# CSI2-ZCU106-EVK-1_Rev01.net
KiCad netlist of a schematic drawn in Altium Designer
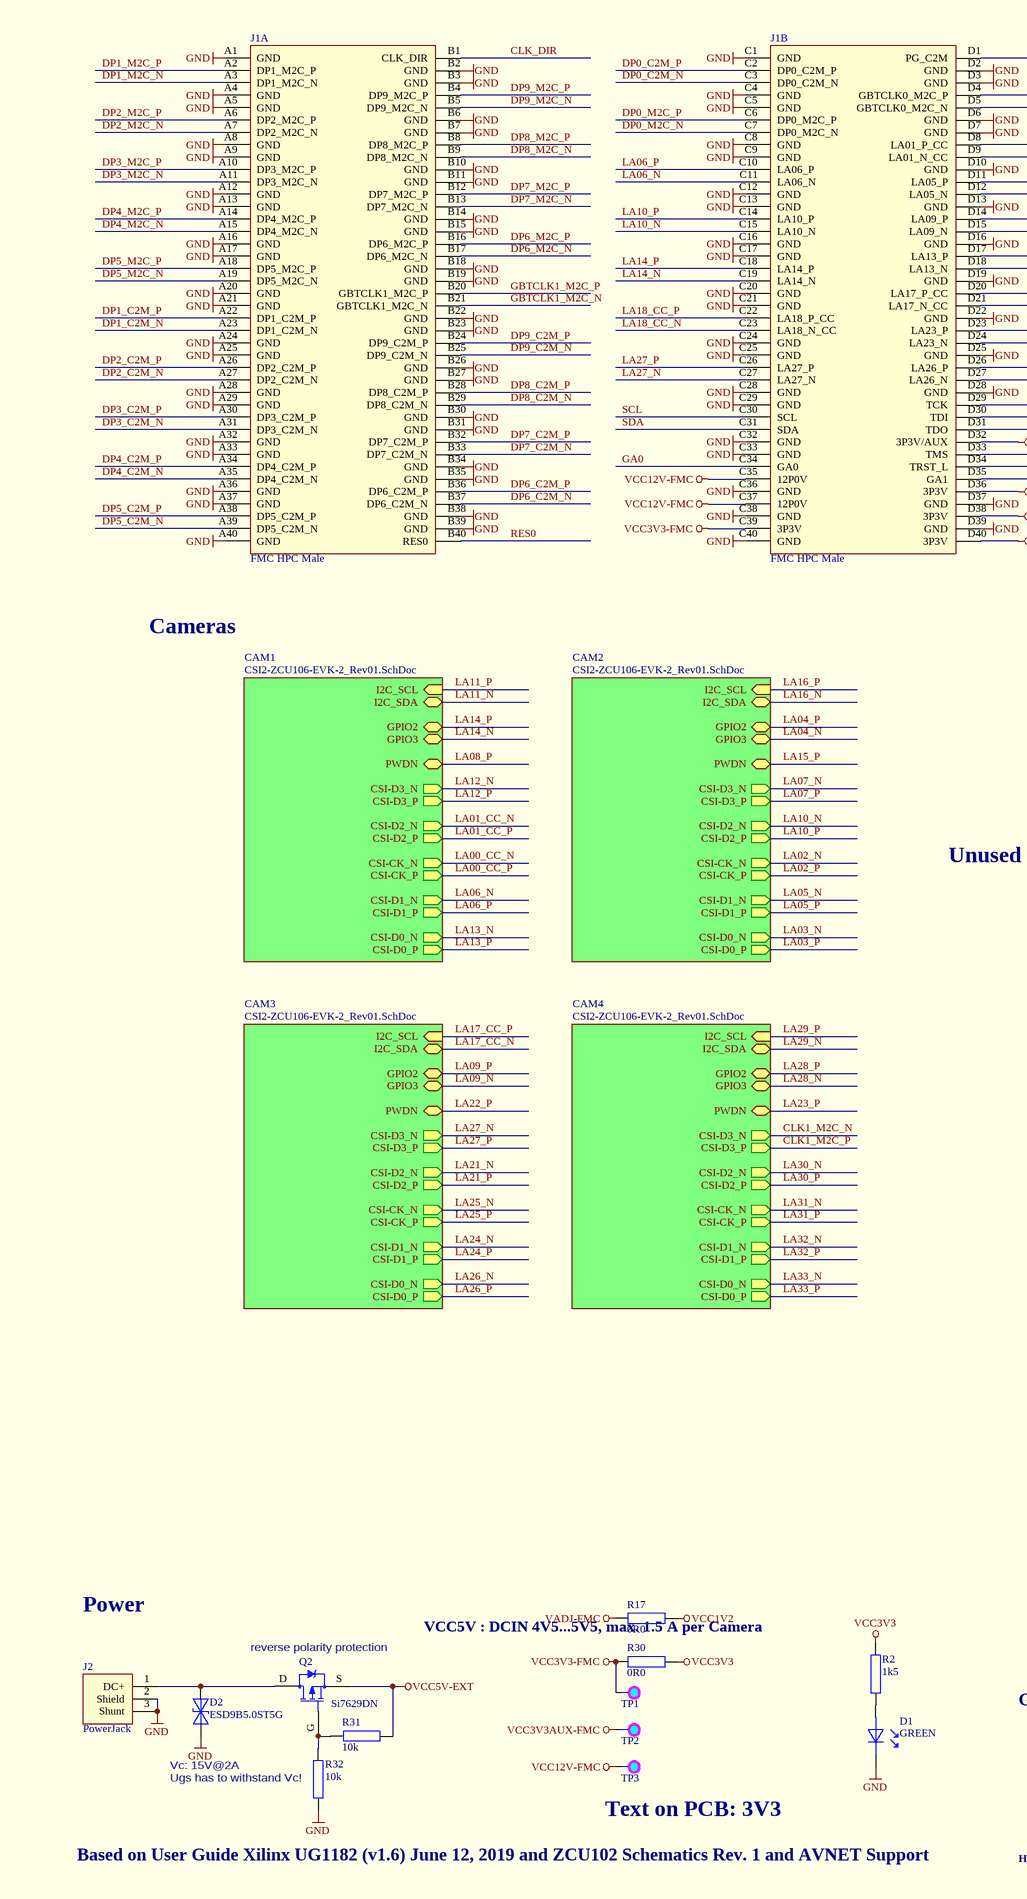
[diagram p0: CSI2-ZCU106-EVK-1_Rev01.SchDoc, left]
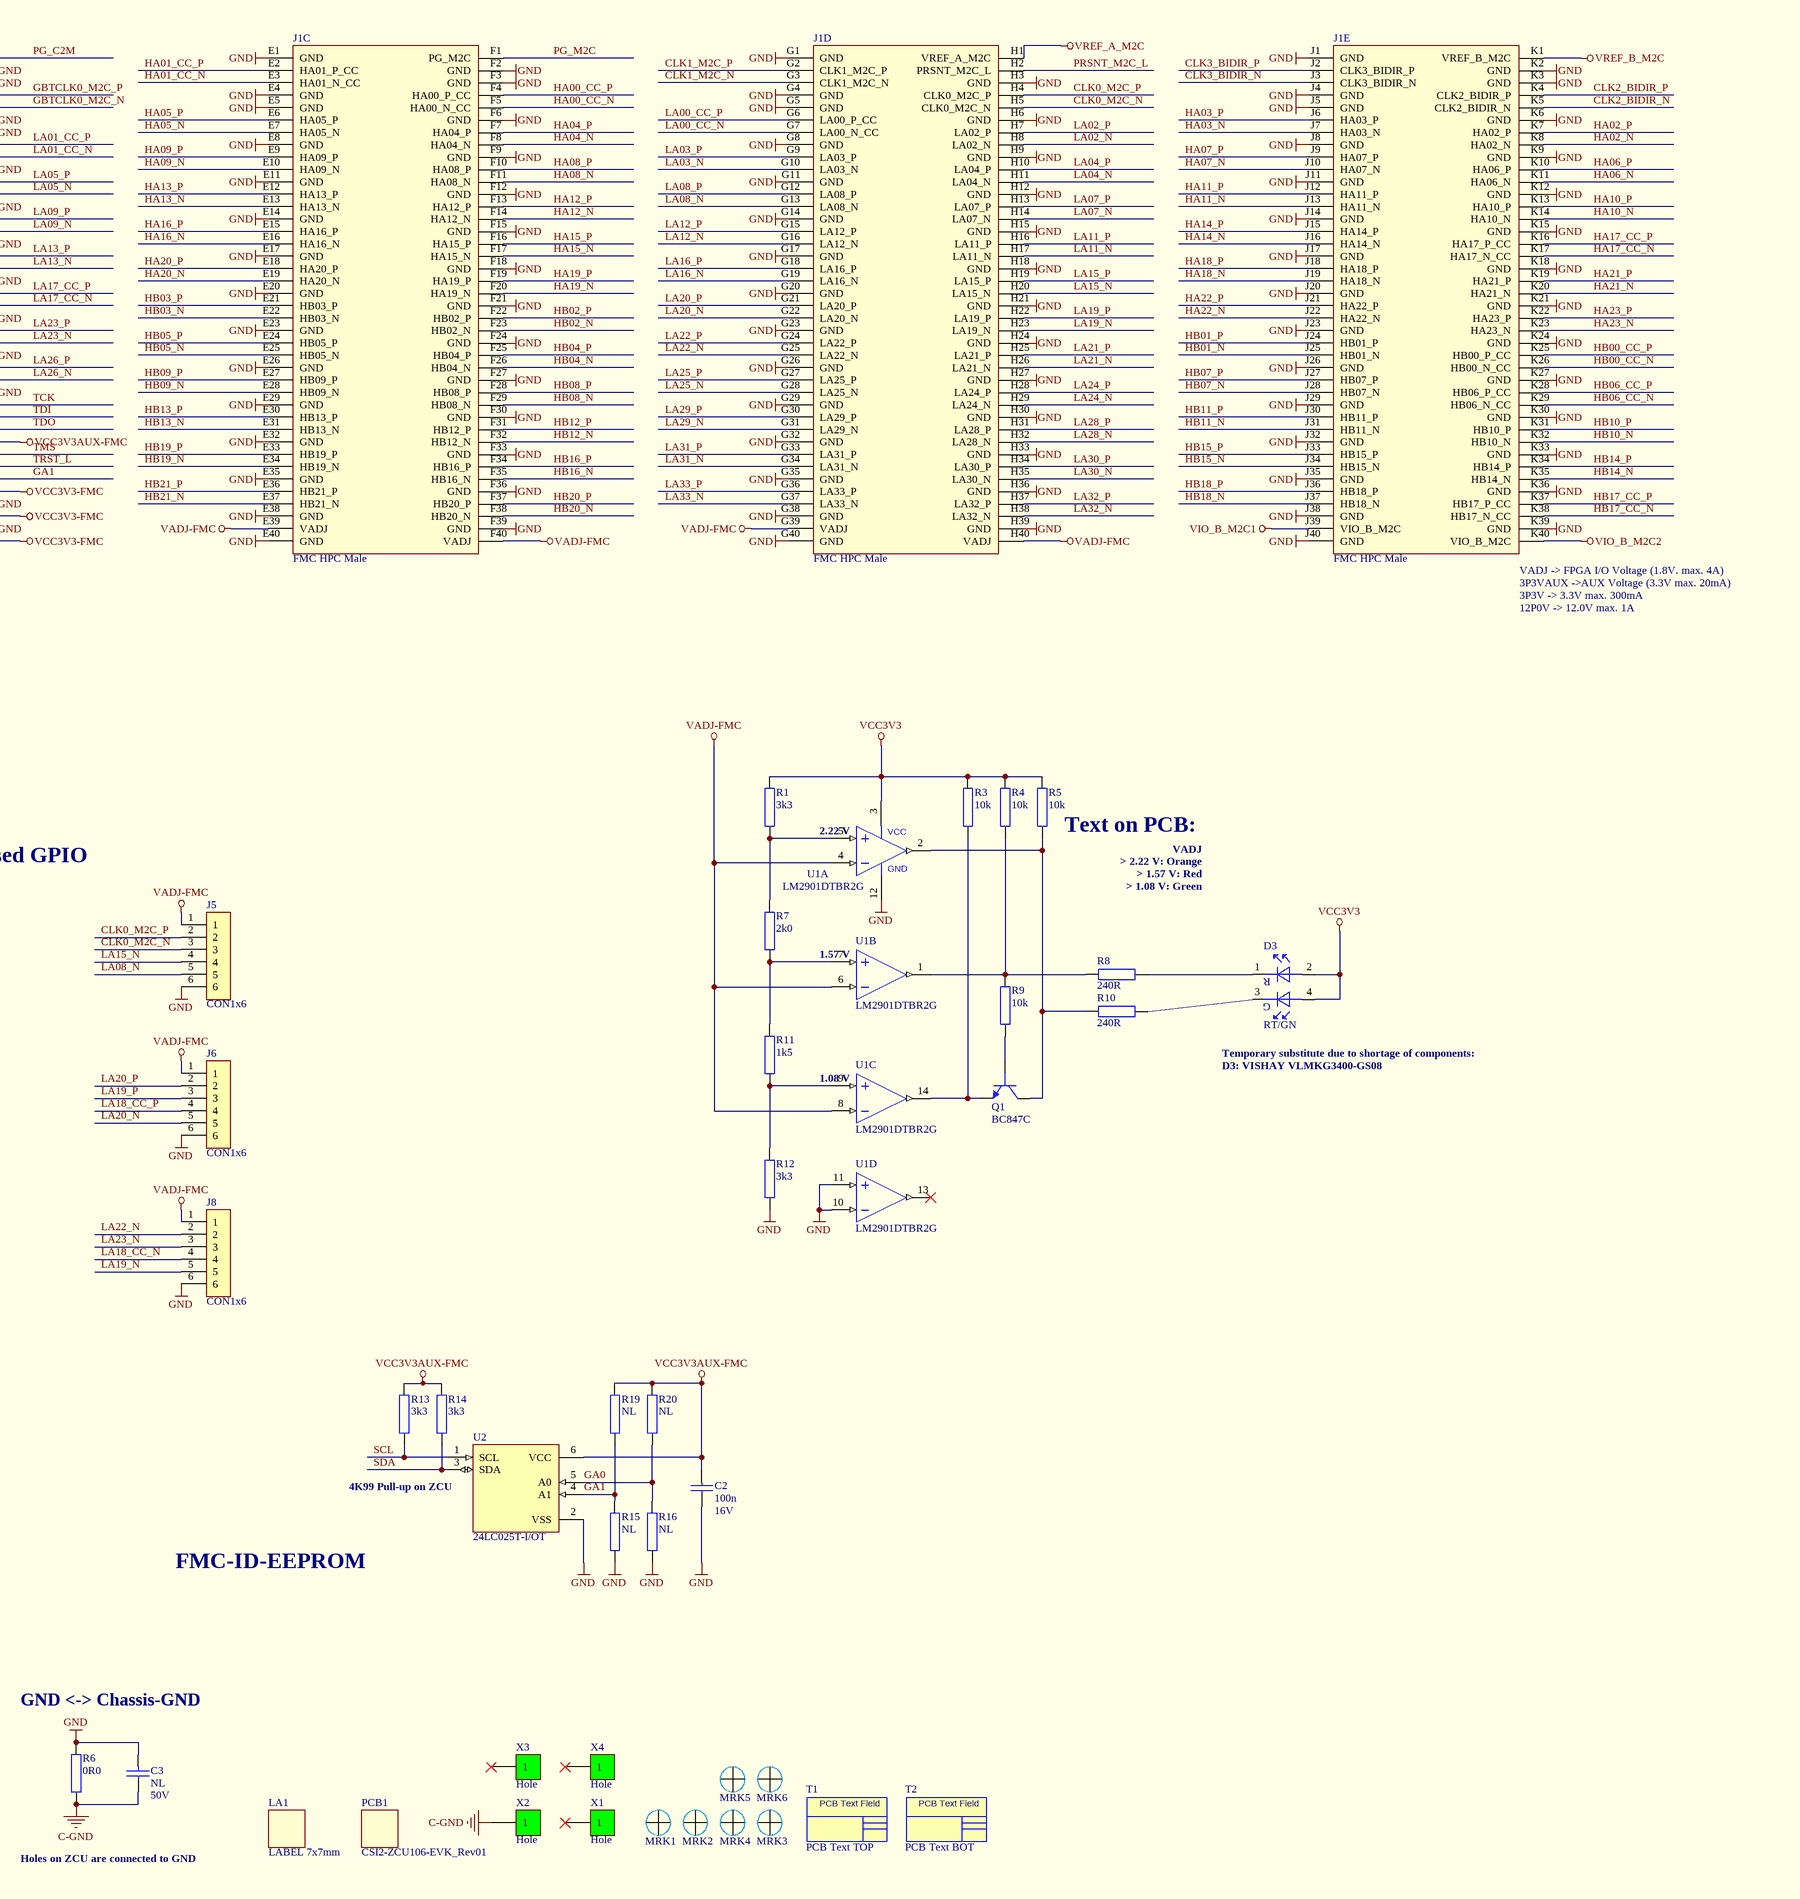
[diagram p1: CSI2-ZCU106-EVK-1_Rev01.SchDoc, right]

(export (version "E")
  (design (tool "Eeschema 10.0.6"))
  (components
    (comp (ref "C2")
      (value "100n")
      (footprint "C-0402_0.55")
      (description "Capacitor Ceramic SMD/0402/16V/X7R/10%")
      (fields
        (field (name "KHK PART NUMBER") "K8340114")
        (field (name "MANUFACTURER") "several")
        (field (name "VOLTAGE") "16V")
      )
      (libsource (lib "Passive") (part "C 100N 10% 16V X7R 402"))
    )
    (comp (ref "C3")
      (value "NL")
      (footprint "C-0603_1.0")
      (description "Capacitor Ceramic SMD/0603/50V/X7R/10%")
      (fields
        (field (name "MANUFACTURER") "several")
        (field (name "TOLERANCE") "10%")
        (field (name "VOLTAGE") "50V")
      )
      (libsource (lib "AVT_KHK_Lib") (part "C X 0603"))
    )
    (comp (ref "D1")
      (value "GREEN")
      (footprint "D-0603-LED")
      (description "Chip LED green 430mcd")
      (fields (field (name "KHK PART NUMBER") "8172") (field (name "MANUFACTURER") "Würth"))
      (libsource (lib "AVT_KHK_Lib") (part "D LED 0603 green"))
    )
    (comp (ref "D2")
      (value "ESD9B5.0ST5G")
      (footprint "D-SOD923")
      (description "DIODE TVS; 400W; 5.8-7.8V; BIDIRECT")
      (fields (field (name "KHK PART NUMBER") "7250") (field (name "MANUFACTURER") "ON Semiconductor"))
      (libsource (lib "AVT_KHK_Lib") (part "D ESD9B5.0ST5G"))
    )
    (comp (ref "D3")
      (value "RT/GN")
      (footprint "LED-PLCC4")
      (description "LED red/green")
      (fields (field (name "KHK PART NUMBER") "11105") (field (name "MANUFACTURER") "OSRAM"))
      (libsource (lib "Bipolar") (part "D LSG T67K-JL-1+HK-1"))
    )
    (comp (ref "J1")
      (value "FMC HPC Male")
      (footprint "J-ASP-134488-01")
      (description "CON FMC HPC MALE 10MM")
      (fields
        (field (name "MANUFACTURER") "Samtec")
        (field (name "MANUFACTURER PART NUMBER") "ASP-134488-01")
      )
      (libsource (lib "Connector") (part "CON FMC HPC Male"))
    )
    (comp (ref "J2")
      (value "PowerJack")
      (footprint "CON_RAPC722")
      (description "Switchcraft PowerJack RAPC722 / 2.1mm (Inner) / 6mm (Outer)")
      (fields (field (name "KHK PART NUMBER") "K7600556") (field (name "MANUFACTURER") "Switchcraft"))
      (libsource (lib "AVT_KHK_Lib") (part "CON RAPC722"))
    )
    (comp (ref "J5")
      (value "CON1x6")
      (footprint "CON 1x6 RM2.54")
      (fields (field (name "MANUFACTURER") "several") (field (name "KHK PART NUMBER") "15686"))
      (libsource (lib "Connector") (part "CON 1x6 2.54 several"))
    )
    (comp (ref "J6")
      (value "CON1x6")
      (footprint "CON 1x6 RM2.54")
      (fields (field (name "MANUFACTURER") "several") (field (name "KHK PART NUMBER") "15686"))
      (libsource (lib "Connector") (part "CON 1x6 2.54 several"))
    )
    (comp (ref "J8")
      (value "CON1x6")
      (footprint "CON 1x6 RM2.54")
      (fields (field (name "MANUFACTURER") "several") (field (name "KHK PART NUMBER") "15686"))
      (libsource (lib "Connector") (part "CON 1x6 2.54 several"))
    )
    (comp (ref "LA1")
      (value "LABEL 7x7mm")
      (footprint "PCB LABEL 7x7")
      (fields (field (name "MANUFACTURER") "several"))
      (libsource (lib "Misc") (part "PCB LABEL 7x7"))
    )
    (comp (ref "MRK1")
      (value "Marker Single Layer")
      (footprint "PCB_Marker_Pad_top")
      (description "Position Marker for PCBs")
      (libsource (lib "AVT_KHK_Lib") (part "PCB Marker Pad Single Layer"))
    )
    (comp (ref "MRK2")
      (value "Marker Single Layer")
      (footprint "PCB_Marker_Pad_top")
      (description "Position Marker for PCBs")
      (libsource (lib "AVT_KHK_Lib") (part "PCB Marker Pad Single Layer"))
    )
    (comp (ref "MRK3")
      (value "Marker Single Layer")
      (footprint "PCB_Marker_Pad_top")
      (description "Position Marker for PCBs")
      (libsource (lib "AVT_KHK_Lib") (part "PCB Marker Pad Single Layer"))
    )
    (comp (ref "MRK4")
      (value "Marker Single Layer")
      (footprint "PCB_Marker_Pad_top")
      (description "Position Marker for PCBs")
      (libsource (lib "AVT_KHK_Lib") (part "PCB Marker Pad Single Layer"))
    )
    (comp (ref "MRK5")
      (value "Marker Single Layer")
      (footprint "PCB_Marker_Pad_top")
      (description "Position Marker for PCBs")
      (libsource (lib "AVT_KHK_Lib") (part "PCB Marker Pad Single Layer"))
    )
    (comp (ref "MRK6")
      (value "Marker Single Layer")
      (footprint "PCB_Marker_Pad_top")
      (description "Position Marker for PCBs")
      (libsource (lib "AVT_KHK_Lib") (part "PCB Marker Pad Single Layer"))
    )
    (comp (ref "PCB1")
      (value "CSI2-ZCU106-EVK_Rev01")
      (description "PCB ML04SF")
      (fields (field (name "MANUFACTURER") "several"))
      (libsource (lib "AVT_KHK_Lib") (part "PCB"))
    )
    (comp (ref "Q1")
      (value "BC847C")
      (footprint "IC-SOT23-3")
      (description "TRANSISTOR NPN 100mA 45V")
      (fields (field (name "MANUFACTURER") "several") (field (name "KHK PART NUMBER") "16587"))
      (libsource (lib "Bipolar") (part "Q BC847C SOT23"))
    )
    (comp (ref "Q2")
      (value "Si7629DN")
      (footprint "IC-POWERPAK_1212-8_3.4x3.4x1.1")
      (description "P-Channel MOSFET 20V")
      (fields (field (name "KHK PART NUMBER") "3619") (field (name "MANUFACTURER") "Vishay"))
      (libsource (lib "AVT_KHK_Lib") (part "Q Si7629DN"))
    )
    (comp (ref "R1")
      (value "3k3")
      (footprint "R-0402_0.4")
      (description "Standard Resistor SMD/0402/1%/63mW/TK100")
      (fields (field (name "KHK PART NUMBER") "K8250347") (field (name "MANUFACTURER") "several"))
      (libsource (lib "AVT_KHK_Lib") (part "R 3k3 1% 0402"))
    )
    (comp (ref "R2")
      (value "1k5")
      (footprint "R-0402_0.4")
      (description "Standard Resistor SMD/0402/1%/63mW/TK100")
      (fields (field (name "KHK PART NUMBER") "K8250358") (field (name "MANUFACTURER") "several"))
      (libsource (lib "AVT_KHK_Lib") (part "R 1K5 1% 0402"))
    )
    (comp (ref "R3")
      (value "10k")
      (footprint "R-0402_0.4")
      (description "Standard Resistor SMD/0402/1%/63mW/TK100")
      (fields (field (name "KHK PART NUMBER") "K8250264") (field (name "MANUFACTURER") "several"))
      (libsource (lib "Passive") (part "R 10K 1% 0402"))
    )
    (comp (ref "R4")
      (value "10k")
      (footprint "R-0402_0.4")
      (description "Standard Resistor SMD/0402/1%/63mW/TK100")
      (fields (field (name "KHK PART NUMBER") "K8250264") (field (name "MANUFACTURER") "several"))
      (libsource (lib "Passive") (part "R 10K 1% 0402"))
    )
    (comp (ref "R5")
      (value "10k")
      (footprint "R-0402_0.4")
      (description "Standard Resistor SMD/0402/1%/63mW/TK100")
      (fields (field (name "KHK PART NUMBER") "K8250264") (field (name "MANUFACTURER") "several"))
      (libsource (lib "Passive") (part "R 10K 1% 0402"))
    )
    (comp (ref "R6")
      (value "0R0")
      (footprint "R-0603_0.6")
      (description "Standard Resistor SMD/0603/1%/100mW/TK200")
      (fields (field (name "KHK PART NUMBER") "K8250041") (field (name "MANUFACTURER") "several"))
      (libsource (lib "Passive") (part "R 0R0 1% 0603"))
    )
    (comp (ref "R7")
      (value "2k0")
      (footprint "R-0402_0.4")
      (description "Standard Resistor SMD/0402/1%/63mW/TK100")
      (fields (field (name "KHK PART NUMBER") "K8250311") (field (name "MANUFACTURER") "several"))
      (libsource (lib "Passive") (part "R 2k0 1% 0402"))
    )
    (comp (ref "R8")
      (value "240R")
      (footprint "R-0402_0.4")
      (description "Standard Resistor SMD/0402/1%/63mW/TK100")
      (fields (field (name "KHK PART NUMBER") "7256") (field (name "MANUFACTURER") "several"))
      (libsource (lib "AVT_KHK_Lib") (part "R 240R 1% 0402"))
    )
    (comp (ref "R9")
      (value "10k")
      (footprint "R-0402_0.4")
      (description "Standard Resistor SMD/0402/1%/63mW/TK100")
      (fields (field (name "KHK PART NUMBER") "K8250264") (field (name "MANUFACTURER") "several"))
      (libsource (lib "Passive") (part "R 10K 1% 0402"))
    )
    (comp (ref "R10")
      (value "240R")
      (footprint "R-0402_0.4")
      (description "Standard Resistor SMD/0402/1%/63mW/TK100")
      (fields (field (name "KHK PART NUMBER") "7256") (field (name "MANUFACTURER") "several"))
      (libsource (lib "AVT_KHK_Lib") (part "R 240R 1% 0402"))
    )
    (comp (ref "R11")
      (value "1k5")
      (footprint "R-0402_0.4")
      (description "Standard Resistor SMD/0402/1%/63mW/TK100")
      (fields (field (name "KHK PART NUMBER") "K8250358") (field (name "MANUFACTURER") "several"))
      (libsource (lib "Passive") (part "R 1K5 1% 0402"))
    )
    (comp (ref "R12")
      (value "3k3")
      (footprint "R-0402_0.4")
      (description "Standard Resistor SMD/0402/1%/63mW/TK100")
      (fields (field (name "KHK PART NUMBER") "K8250347") (field (name "MANUFACTURER") "several"))
      (libsource (lib "AVT_KHK_Lib") (part "R 3k3 1% 0402"))
    )
    (comp (ref "R13")
      (value "3k3")
      (footprint "R-0402_0.4")
      (description "Standard Resistor SMD/0402/1%/63mW/TK100")
      (fields (field (name "KHK PART NUMBER") "K8250347") (field (name "MANUFACTURER") "several"))
      (libsource (lib "AVT_KHK_Lib") (part "R 3k3 1% 0402"))
    )
    (comp (ref "R14")
      (value "3k3")
      (footprint "R-0402_0.4")
      (description "Standard Resistor SMD/0402/1%/63mW/TK100")
      (fields (field (name "KHK PART NUMBER") "K8250347") (field (name "MANUFACTURER") "several"))
      (libsource (lib "AVT_KHK_Lib") (part "R 3k3 1% 0402"))
    )
    (comp (ref "R15")
      (value "NL")
      (footprint "R-0603_0.6")
      (description "Standard Resistor SMD/0603/1%/100mW/TK200")
      (fields (field (name "TOLERANCE") "1%"))
      (libsource (lib "AVT_KHK_Lib") (part "R X 0603"))
    )
    (comp (ref "R16")
      (value "NL")
      (footprint "R-0603_0.6")
      (description "Standard Resistor SMD/0603/1%/100mW/TK200")
      (fields (field (name "TOLERANCE") "1%"))
      (libsource (lib "AVT_KHK_Lib") (part "R X 0603"))
    )
    (comp (ref "R17")
      (value "0R0")
      (footprint "R-0603_0.6")
      (description "Standard Resistor SMD/0603/1%/100mW/TK200")
      (fields (field (name "KHK PART NUMBER") "K8250041") (field (name "MANUFACTURER") "several"))
      (libsource (lib "Passive") (part "R 0R0 1% 0603"))
    )
    (comp (ref "R19")
      (value "NL")
      (footprint "R-0603_0.6")
      (description "Standard Resistor SMD/0603/1%/100mW/TK200")
      (fields (field (name "TOLERANCE") "1%"))
      (libsource (lib "AVT_KHK_Lib") (part "R X 0603"))
    )
    (comp (ref "R20")
      (value "NL")
      (footprint "R-0603_0.6")
      (description "Standard Resistor SMD/0603/1%/100mW/TK200")
      (fields (field (name "TOLERANCE") "1%"))
      (libsource (lib "AVT_KHK_Lib") (part "R X 0603"))
    )
    (comp (ref "R30")
      (value "0R0")
      (footprint "R-0603_0.6")
      (description "Standard Resistor SMD/0603/1%/100mW/TK200")
      (fields (field (name "KHK PART NUMBER") "K8250041") (field (name "MANUFACTURER") "several"))
      (libsource (lib "Passive") (part "R 0R0 1% 0603"))
    )
    (comp (ref "R31")
      (value "10k")
      (footprint "R-0402_0.4")
      (description "Standard Resistor SMD/0402/1%/63mW/TK100")
      (fields (field (name "KHK PART NUMBER") "K8250264") (field (name "MANUFACTURER") "several"))
      (libsource (lib "Passive") (part "R 10K 1% 0402"))
    )
    (comp (ref "R32")
      (value "10k")
      (footprint "R-0402_0.4")
      (description "Standard Resistor SMD/0402/1%/63mW/TK100")
      (fields (field (name "KHK PART NUMBER") "K8250264") (field (name "MANUFACTURER") "several"))
      (libsource (lib "Passive") (part "R 10K 1% 0402"))
    )
    (comp (ref "T1")
      (value "PCB Text TOP")
      (footprint "PCB TEXTFIELD TOP 2")
      (description "PCB Textfield TOP")
      (libsource (lib "AVT_KHK_Lib") (part "PCB TEXT FIELD TOP"))
    )
    (comp (ref "T2")
      (value "PCB Text BOT")
      (footprint "PCB TEXTFIELD BOT 2")
      (description "PCB Textfield BOT")
      (libsource (lib "AVT_KHK_Lib") (part "PCB TEXT FIELD BOT"))
    )
    (comp (ref "TP1")
      (value "TP")
      (footprint "TP_16_10")
      (description "Testpoint: Pad=1,6mm; Hole=1,0mm")
      (libsource (lib "AVT_KHK_Lib") (part "TP_16_10"))
    )
    (comp (ref "TP2")
      (value "TP")
      (footprint "TP_16_10")
      (description "Testpoint: Pad=1,6mm; Hole=1,0mm")
      (libsource (lib "AVT_KHK_Lib") (part "TP_16_10"))
    )
    (comp (ref "TP3")
      (value "TP")
      (footprint "TP_16_10")
      (description "Testpoint: Pad=1,6mm; Hole=1,0mm")
      (libsource (lib "AVT_KHK_Lib") (part "TP_16_10"))
    )
    (comp (ref "U1")
      (value "LM2901DTBR2G")
      (footprint "IC-SO14_5.1x6.6x1.2")
      (description "QUAD COMPERATOR")
      (fields (field (name "MANUFACTURER") "ON Semi"))
      (libsource (lib "Amp") (part "IC LM2901DTBR2G"))
    )
    (comp (ref "U2")
      (value "24LC025T-I/OT")
      (footprint "IC-SOT23-6")
      (description "2K I2C Serial EEPROM 2V5-5V5")
      (fields (field (name "KHK PART NUMBER") "9217") (field (name "MANUFACTURER") "Microchip"))
      (libsource (lib "Memory") (part "IC 24LC025T-I/OT"))
    )
    (comp (ref "X1")
      (value "Hole")
      (footprint "HOLE-2.6-5.0-DK")
      (description "HOLE M2.5")
      (libsource (lib "AVT_KHK_Lib") (part "PCB HOLE M2.5-5-DK"))
    )
    (comp (ref "X2")
      (value "Hole")
      (footprint "HOLE-2.6-5.0-DK")
      (description "HOLE M2.5")
      (libsource (lib "AVT_KHK_Lib") (part "PCB HOLE M2.5-5-DK"))
    )
    (comp (ref "X3")
      (value "Hole")
      (footprint "HOLE-2.6-5.0-DK")
      (description "HOLE M2.5")
      (libsource (lib "AVT_KHK_Lib") (part "PCB HOLE M2.5-5-DK"))
    )
    (comp (ref "X4")
      (value "Hole")
      (footprint "HOLE-2.6-5.0-DK")
      (description "HOLE M2.5")
      (libsource (lib "AVT_KHK_Lib") (part "PCB HOLE M2.5-5-DK"))
    )
  )
  (nets
    (net (code "1") (name "/CLK0_M2C_N") (class "Default")
      (node (ref "J1") (pin "H5") (pinfunction "CLK0_M2C_N_H5") (pintype "passive"))
      (node (ref "J5") (pin "3") (pinfunction "3_3") (pintype "passive"))
    )
    (net (code "2") (name "/CLK0_M2C_P") (class "Default")
      (node (ref "J1") (pin "H4") (pinfunction "CLK0_M2C_P_H4") (pintype "passive"))
      (node (ref "J5") (pin "2") (pinfunction "2_2") (pintype "passive"))
    )
    (net (code "3") (name "/CLK1_M2C_N") (class "Default")
      (node (ref "J1") (pin "G3") (pinfunction "CLK1_M2C_N_G3") (pintype "passive"))
    )
    (net (code "4") (name "/CLK1_M2C_P") (class "Default")
      (node (ref "J1") (pin "G2") (pinfunction "CLK1_M2C_P_G2") (pintype "passive"))
    )
    (net (code "5") (name "/CLK2_BIDIR_N") (class "Default")
      (node (ref "J1") (pin "K5") (pinfunction "CLK2_BIDIR_N_K5") (pintype "passive"))
    )
    (net (code "6") (name "/CLK2_BIDIR_P") (class "Default")
      (node (ref "J1") (pin "K4") (pinfunction "CLK2_BIDIR_P_K4") (pintype "passive"))
    )
    (net (code "7") (name "/CLK3_BIDIR_N") (class "Default")
      (node (ref "J1") (pin "J3") (pinfunction "CLK3_BIDIR_N_J3") (pintype "passive"))
    )
    (net (code "8") (name "/CLK3_BIDIR_P") (class "Default")
      (node (ref "J1") (pin "J2") (pinfunction "CLK3_BIDIR_P_J2") (pintype "passive"))
    )
    (net (code "9") (name "/CLK_DIR") (class "Default")
      (node (ref "J1") (pin "B1") (pinfunction "CLK_DIR_B1") (pintype "passive"))
    )
    (net (code "10") (name "/DP0_C2M_N") (class "Default")
      (node (ref "J1") (pin "C3") (pinfunction "DP0_C2M_N_C3") (pintype "passive"))
    )
    (net (code "11") (name "/DP0_C2M_P") (class "Default")
      (node (ref "J1") (pin "C2") (pinfunction "DP0_C2M_P_C2") (pintype "passive"))
    )
    (net (code "12") (name "/DP0_M2C_N") (class "Default")
      (node (ref "J1") (pin "C7") (pinfunction "DP0_M2C_N_C7") (pintype "passive"))
    )
    (net (code "13") (name "/DP0_M2C_P") (class "Default")
      (node (ref "J1") (pin "C6") (pinfunction "DP0_M2C_P_C6") (pintype "passive"))
    )
    (net (code "14") (name "/DP1_C2M_N") (class "Default")
      (node (ref "J1") (pin "A23") (pinfunction "DP1_C2M_N_A23") (pintype "passive"))
    )
    (net (code "15") (name "/DP1_C2M_P") (class "Default")
      (node (ref "J1") (pin "A22") (pinfunction "DP1_C2M_P_A22") (pintype "passive"))
    )
    (net (code "16") (name "/DP1_M2C_N") (class "Default")
      (node (ref "J1") (pin "A3") (pinfunction "DP1_M2C_N_A3") (pintype "passive"))
    )
    (net (code "17") (name "/DP1_M2C_P") (class "Default")
      (node (ref "J1") (pin "A2") (pinfunction "DP1_M2C_P_A2") (pintype "passive"))
    )
    (net (code "18") (name "/DP2_C2M_N") (class "Default")
      (node (ref "J1") (pin "A27") (pinfunction "DP2_C2M_N_A27") (pintype "passive"))
    )
    (net (code "19") (name "/DP2_C2M_P") (class "Default")
      (node (ref "J1") (pin "A26") (pinfunction "DP2_C2M_P_A26") (pintype "passive"))
    )
    (net (code "20") (name "/DP2_M2C_N") (class "Default")
      (node (ref "J1") (pin "A7") (pinfunction "DP2_M2C_N_A7") (pintype "passive"))
    )
    (net (code "21") (name "/DP2_M2C_P") (class "Default")
      (node (ref "J1") (pin "A6") (pinfunction "DP2_M2C_P_A6") (pintype "passive"))
    )
    (net (code "22") (name "/DP3_C2M_N") (class "Default")
      (node (ref "J1") (pin "A31") (pinfunction "DP3_C2M_N_A31") (pintype "passive"))
    )
    (net (code "23") (name "/DP3_C2M_P") (class "Default")
      (node (ref "J1") (pin "A30") (pinfunction "DP3_C2M_P_A30") (pintype "passive"))
    )
    (net (code "24") (name "/DP3_M2C_N") (class "Default")
      (node (ref "J1") (pin "A11") (pinfunction "DP3_M2C_N_A11") (pintype "passive"))
    )
    (net (code "25") (name "/DP3_M2C_P") (class "Default")
      (node (ref "J1") (pin "A10") (pinfunction "DP3_M2C_P_A10") (pintype "passive"))
    )
    (net (code "26") (name "/DP4_C2M_N") (class "Default")
      (node (ref "J1") (pin "A35") (pinfunction "DP4_C2M_N_A35") (pintype "passive"))
    )
    (net (code "27") (name "/DP4_C2M_P") (class "Default")
      (node (ref "J1") (pin "A34") (pinfunction "DP4_C2M_P_A34") (pintype "passive"))
    )
    (net (code "28") (name "/DP4_M2C_N") (class "Default")
      (node (ref "J1") (pin "A15") (pinfunction "DP4_M2C_N_A15") (pintype "passive"))
    )
    (net (code "29") (name "/DP4_M2C_P") (class "Default")
      (node (ref "J1") (pin "A14") (pinfunction "DP4_M2C_P_A14") (pintype "passive"))
    )
    (net (code "30") (name "/DP5_C2M_N") (class "Default")
      (node (ref "J1") (pin "A39") (pinfunction "DP5_C2M_N_A39") (pintype "passive"))
    )
    (net (code "31") (name "/DP5_C2M_P") (class "Default")
      (node (ref "J1") (pin "A38") (pinfunction "DP5_C2M_P_A38") (pintype "passive"))
    )
    (net (code "32") (name "/DP5_M2C_N") (class "Default")
      (node (ref "J1") (pin "A19") (pinfunction "DP5_M2C_N_A19") (pintype "passive"))
    )
    (net (code "33") (name "/DP5_M2C_P") (class "Default")
      (node (ref "J1") (pin "A18") (pinfunction "DP5_M2C_P_A18") (pintype "passive"))
    )
    (net (code "34") (name "/DP6_C2M_N") (class "Default")
      (node (ref "J1") (pin "B37") (pinfunction "DP6_C2M_N_B37") (pintype "passive"))
    )
    (net (code "35") (name "/DP6_C2M_P") (class "Default")
      (node (ref "J1") (pin "B36") (pinfunction "DP6_C2M_P_B36") (pintype "passive"))
    )
    (net (code "36") (name "/DP6_M2C_N") (class "Default")
      (node (ref "J1") (pin "B17") (pinfunction "DP6_M2C_N_B17") (pintype "passive"))
    )
    (net (code "37") (name "/DP6_M2C_P") (class "Default")
      (node (ref "J1") (pin "B16") (pinfunction "DP6_M2C_P_B16") (pintype "passive"))
    )
    (net (code "38") (name "/DP7_C2M_N") (class "Default")
      (node (ref "J1") (pin "B33") (pinfunction "DP7_C2M_N_B33") (pintype "passive"))
    )
    (net (code "39") (name "/DP7_C2M_P") (class "Default")
      (node (ref "J1") (pin "B32") (pinfunction "DP7_C2M_P_B32") (pintype "passive"))
    )
    (net (code "40") (name "/DP7_M2C_N") (class "Default")
      (node (ref "J1") (pin "B13") (pinfunction "DP7_M2C_N_B13") (pintype "passive"))
    )
    (net (code "41") (name "/DP7_M2C_P") (class "Default")
      (node (ref "J1") (pin "B12") (pinfunction "DP7_M2C_P_B12") (pintype "passive"))
    )
    (net (code "42") (name "/DP8_C2M_N") (class "Default")
      (node (ref "J1") (pin "B29") (pinfunction "DP8_C2M_N_B29") (pintype "passive"))
    )
    (net (code "43") (name "/DP8_C2M_P") (class "Default")
      (node (ref "J1") (pin "B28") (pinfunction "DP8_C2M_P_B28") (pintype "passive"))
    )
    (net (code "44") (name "/DP8_M2C_N") (class "Default")
      (node (ref "J1") (pin "B9") (pinfunction "DP8_M2C_N_B9") (pintype "passive"))
    )
    (net (code "45") (name "/DP8_M2C_P") (class "Default")
      (node (ref "J1") (pin "B8") (pinfunction "DP8_M2C_P_B8") (pintype "passive"))
    )
    (net (code "46") (name "/DP9_C2M_N") (class "Default")
      (node (ref "J1") (pin "B25") (pinfunction "DP9_C2M_N_B25") (pintype "passive"))
    )
    (net (code "47") (name "/DP9_C2M_P") (class "Default")
      (node (ref "J1") (pin "B24") (pinfunction "DP9_C2M_P_B24") (pintype "passive"))
    )
    (net (code "48") (name "/DP9_M2C_N") (class "Default")
      (node (ref "J1") (pin "B5") (pinfunction "DP9_M2C_N_B5") (pintype "passive"))
    )
    (net (code "49") (name "/DP9_M2C_P") (class "Default")
      (node (ref "J1") (pin "B4") (pinfunction "DP9_M2C_P_B4") (pintype "passive"))
    )
    (net (code "50") (name "/GA0") (class "Default")
      (node (ref "J1") (pin "C34") (pinfunction "GA0_C34") (pintype "passive"))
      (node (ref "R16") (pin "1") (pinfunction "1_1") (pintype "passive"))
      (node (ref "R20") (pin "2") (pinfunction "2_2") (pintype "passive"))
      (node (ref "U2") (pin "5") (pinfunction "A0_5") (pintype "input"))
    )
    (net (code "51") (name "/GA1") (class "Default")
      (node (ref "J1") (pin "D35") (pinfunction "GA1_D35") (pintype "passive"))
      (node (ref "R15") (pin "1") (pinfunction "1_1") (pintype "passive"))
      (node (ref "R19") (pin "2") (pinfunction "2_2") (pintype "passive"))
      (node (ref "U2") (pin "4") (pinfunction "A1_4") (pintype "input"))
    )
    (net (code "52") (name "/GBTCLK0_M2C_N") (class "Default")
      (node (ref "J1") (pin "D5") (pinfunction "GBTCLK0_M2C_N_D5") (pintype "passive"))
    )
    (net (code "53") (name "/GBTCLK0_M2C_P") (class "Default")
      (node (ref "J1") (pin "D4") (pinfunction "GBTCLK0_M2C_P_D4") (pintype "passive"))
    )
    (net (code "54") (name "/GBTCLK1_M2C_N") (class "Default")
      (node (ref "J1") (pin "B21") (pinfunction "GBTCLK1_M2C_N_B21") (pintype "passive"))
    )
    (net (code "55") (name "/GBTCLK1_M2C_P") (class "Default")
      (node (ref "J1") (pin "B20") (pinfunction "GBTCLK1_M2C_P_B20") (pintype "passive"))
    )
    (net (code "56") (name "/HA00_CC_N") (class "Default")
      (node (ref "J1") (pin "F5") (pinfunction "HA00_N_CC_F5") (pintype "passive"))
    )
    (net (code "57") (name "/HA00_CC_P") (class "Default")
      (node (ref "J1") (pin "F4") (pinfunction "HA00_P_CC_F4") (pintype "passive"))
    )
    (net (code "58") (name "/HA01_CC_N") (class "Default")
      (node (ref "J1") (pin "E3") (pinfunction "HA01_N_CC_E3") (pintype "passive"))
    )
    (net (code "59") (name "/HA01_CC_P") (class "Default")
      (node (ref "J1") (pin "E2") (pinfunction "HA01_P_CC_E2") (pintype "passive"))
    )
    (net (code "60") (name "/HA02_N") (class "Default")
      (node (ref "J1") (pin "K8") (pinfunction "HA02_N_K8") (pintype "passive"))
    )
    (net (code "61") (name "/HA02_P") (class "Default")
      (node (ref "J1") (pin "K7") (pinfunction "HA02_P_K7") (pintype "passive"))
    )
    (net (code "62") (name "/HA03_N") (class "Default")
      (node (ref "J1") (pin "J7") (pinfunction "HA03_N_J7") (pintype "passive"))
    )
    (net (code "63") (name "/HA03_P") (class "Default")
      (node (ref "J1") (pin "J6") (pinfunction "HA03_P_J6") (pintype "passive"))
    )
    (net (code "64") (name "/HA04_N") (class "Default")
      (node (ref "J1") (pin "F8") (pinfunction "HA04_N_F8") (pintype "passive"))
    )
    (net (code "65") (name "/HA04_P") (class "Default")
      (node (ref "J1") (pin "F7") (pinfunction "HA04_P_F7") (pintype "passive"))
    )
    (net (code "66") (name "/HA05_N") (class "Default")
      (node (ref "J1") (pin "E7") (pinfunction "HA05_N_E7") (pintype "passive"))
    )
    (net (code "67") (name "/HA05_P") (class "Default")
      (node (ref "J1") (pin "E6") (pinfunction "HA05_P_E6") (pintype "passive"))
    )
    (net (code "68") (name "/HA06_N") (class "Default")
      (node (ref "J1") (pin "K11") (pinfunction "HA06_N_K11") (pintype "passive"))
    )
    (net (code "69") (name "/HA06_P") (class "Default")
      (node (ref "J1") (pin "K10") (pinfunction "HA06_P_K10") (pintype "passive"))
    )
    (net (code "70") (name "/HA07_N") (class "Default")
      (node (ref "J1") (pin "J10") (pinfunction "HA07_N_J10") (pintype "passive"))
    )
    (net (code "71") (name "/HA07_P") (class "Default")
      (node (ref "J1") (pin "J9") (pinfunction "HA07_P_J9") (pintype "passive"))
    )
    (net (code "72") (name "/HA08_N") (class "Default")
      (node (ref "J1") (pin "F11") (pinfunction "HA08_N_F11") (pintype "passive"))
    )
    (net (code "73") (name "/HA08_P") (class "Default")
      (node (ref "J1") (pin "F10") (pinfunction "HA08_P_F10") (pintype "passive"))
    )
    (net (code "74") (name "/HA09_N") (class "Default")
      (node (ref "J1") (pin "E10") (pinfunction "HA09_N_E10") (pintype "passive"))
    )
    (net (code "75") (name "/HA09_P") (class "Default")
      (node (ref "J1") (pin "E9") (pinfunction "HA09_P_E9") (pintype "passive"))
    )
    (net (code "76") (name "/HA10_N") (class "Default")
      (node (ref "J1") (pin "K14") (pinfunction "HA10_N_K14") (pintype "passive"))
    )
    (net (code "77") (name "/HA10_P") (class "Default")
      (node (ref "J1") (pin "K13") (pinfunction "HA10_P_K13") (pintype "passive"))
    )
    (net (code "78") (name "/HA11_N") (class "Default")
      (node (ref "J1") (pin "J13") (pinfunction "HA11_N_J13") (pintype "passive"))
    )
    (net (code "79") (name "/HA11_P") (class "Default")
      (node (ref "J1") (pin "J12") (pinfunction "HA11_P_J12") (pintype "passive"))
    )
    (net (code "80") (name "/HA12_N") (class "Default")
      (node (ref "J1") (pin "F14") (pinfunction "HA12_N_F14") (pintype "passive"))
    )
    (net (code "81") (name "/HA12_P") (class "Default")
      (node (ref "J1") (pin "F13") (pinfunction "HA12_P_F13") (pintype "passive"))
    )
    (net (code "82") (name "/HA13_N") (class "Default")
      (node (ref "J1") (pin "E13") (pinfunction "HA13_N_E13") (pintype "passive"))
    )
    (net (code "83") (name "/HA13_P") (class "Default")
      (node (ref "J1") (pin "E12") (pinfunction "HA13_P_E12") (pintype "passive"))
    )
    (net (code "84") (name "/HA14_N") (class "Default")
      (node (ref "J1") (pin "J16") (pinfunction "HA14_N_J16") (pintype "passive"))
    )
    (net (code "85") (name "/HA14_P") (class "Default")
      (node (ref "J1") (pin "J15") (pinfunction "HA14_P_J15") (pintype "passive"))
    )
    (net (code "86") (name "/HA15_N") (class "Default")
      (node (ref "J1") (pin "F17") (pinfunction "HA15_N_F17") (pintype "passive"))
    )
    (net (code "87") (name "/HA15_P") (class "Default")
      (node (ref "J1") (pin "F16") (pinfunction "HA15_P_F16") (pintype "passive"))
    )
    (net (code "88") (name "/HA16_N") (class "Default")
      (node (ref "J1") (pin "E16") (pinfunction "HA16_N_E16") (pintype "passive"))
    )
    (net (code "89") (name "/HA16_P") (class "Default")
      (node (ref "J1") (pin "E15") (pinfunction "HA16_P_E15") (pintype "passive"))
    )
    (net (code "90") (name "/HA17_CC_N") (class "Default")
      (node (ref "J1") (pin "K17") (pinfunction "HA17_N_CC_K17") (pintype "passive"))
    )
    (net (code "91") (name "/HA17_CC_P") (class "Default")
      (node (ref "J1") (pin "K16") (pinfunction "HA17_P_CC_K16") (pintype "passive"))
    )
    (net (code "92") (name "/HA18_N") (class "Default")
      (node (ref "J1") (pin "J19") (pinfunction "HA18_N_J19") (pintype "passive"))
    )
    (net (code "93") (name "/HA18_P") (class "Default")
      (node (ref "J1") (pin "J18") (pinfunction "HA18_P_J18") (pintype "passive"))
    )
    (net (code "94") (name "/HA19_N") (class "Default")
      (node (ref "J1") (pin "F20") (pinfunction "HA19_N_F20") (pintype "passive"))
    )
    (net (code "95") (name "/HA19_P") (class "Default")
      (node (ref "J1") (pin "F19") (pinfunction "HA19_P_F19") (pintype "passive"))
    )
    (net (code "96") (name "/HA20_N") (class "Default")
      (node (ref "J1") (pin "E19") (pinfunction "HA20_N_E19") (pintype "passive"))
    )
    (net (code "97") (name "/HA20_P") (class "Default")
      (node (ref "J1") (pin "E18") (pinfunction "HA20_P_E18") (pintype "passive"))
    )
    (net (code "98") (name "/HA21_N") (class "Default")
      (node (ref "J1") (pin "K20") (pinfunction "HA21_N_K20") (pintype "passive"))
    )
    (net (code "99") (name "/HA21_P") (class "Default")
      (node (ref "J1") (pin "K19") (pinfunction "HA21_P_K19") (pintype "passive"))
    )
    (net (code "100") (name "/HA22_N") (class "Default")
      (node (ref "J1") (pin "J22") (pinfunction "HA22_N_J22") (pintype "passive"))
    )
    (net (code "101") (name "/HA22_P") (class "Default")
      (node (ref "J1") (pin "J21") (pinfunction "HA22_P_J21") (pintype "passive"))
    )
    (net (code "102") (name "/HA23_N") (class "Default")
      (node (ref "J1") (pin "K23") (pinfunction "HA23_N_K23") (pintype "passive"))
    )
    (net (code "103") (name "/HA23_P") (class "Default")
      (node (ref "J1") (pin "K22") (pinfunction "HA23_P_K22") (pintype "passive"))
    )
    (net (code "104") (name "/HB00_CC_N") (class "Default")
      (node (ref "J1") (pin "K26") (pinfunction "HB00_N_CC_K26") (pintype "passive"))
    )
    (net (code "105") (name "/HB00_CC_P") (class "Default")
      (node (ref "J1") (pin "K25") (pinfunction "HB00_P_CC_K25") (pintype "passive"))
    )
    (net (code "106") (name "/HB01_N") (class "Default")
      (node (ref "J1") (pin "J25") (pinfunction "HB01_N_J25") (pintype "passive"))
    )
    (net (code "107") (name "/HB01_P") (class "Default")
      (node (ref "J1") (pin "J24") (pinfunction "HB01_P_J24") (pintype "passive"))
    )
    (net (code "108") (name "/HB02_N") (class "Default")
      (node (ref "J1") (pin "F23") (pinfunction "HB02_N_F23") (pintype "passive"))
    )
    (net (code "109") (name "/HB02_P") (class "Default")
      (node (ref "J1") (pin "F22") (pinfunction "HB02_P_F22") (pintype "passive"))
    )
    (net (code "110") (name "/HB03_N") (class "Default")
      (node (ref "J1") (pin "E22") (pinfunction "HB03_N_E22") (pintype "passive"))
    )
    (net (code "111") (name "/HB03_P") (class "Default")
      (node (ref "J1") (pin "E21") (pinfunction "HB03_P_E21") (pintype "passive"))
    )
    (net (code "112") (name "/HB04_N") (class "Default")
      (node (ref "J1") (pin "F26") (pinfunction "HB04_N_F26") (pintype "passive"))
    )
    (net (code "113") (name "/HB04_P") (class "Default")
      (node (ref "J1") (pin "F25") (pinfunction "HB04_P_F25") (pintype "passive"))
    )
    (net (code "114") (name "/HB05_N") (class "Default")
      (node (ref "J1") (pin "E25") (pinfunction "HB05_N_E25") (pintype "passive"))
    )
    (net (code "115") (name "/HB05_P") (class "Default")
      (node (ref "J1") (pin "E24") (pinfunction "HB05_P_E24") (pintype "passive"))
    )
    (net (code "116") (name "/HB06_CC_N") (class "Default")
      (node (ref "J1") (pin "K29") (pinfunction "HB06_N_CC_K29") (pintype "passive"))
    )
    (net (code "117") (name "/HB06_CC_P") (class "Default")
      (node (ref "J1") (pin "K28") (pinfunction "HB06_P_CC_K28") (pintype "passive"))
    )
    (net (code "118") (name "/HB07_N") (class "Default")
      (node (ref "J1") (pin "J28") (pinfunction "HB07_N_J28") (pintype "passive"))
    )
    (net (code "119") (name "/HB07_P") (class "Default")
      (node (ref "J1") (pin "J27") (pinfunction "HB07_P_J27") (pintype "passive"))
    )
    (net (code "120") (name "/HB08_N") (class "Default")
      (node (ref "J1") (pin "F29") (pinfunction "HB08_N_F29") (pintype "passive"))
    )
    (net (code "121") (name "/HB08_P") (class "Default")
      (node (ref "J1") (pin "F28") (pinfunction "HB08_P_F28") (pintype "passive"))
    )
    (net (code "122") (name "/HB09_N") (class "Default")
      (node (ref "J1") (pin "E28") (pinfunction "HB09_N_E28") (pintype "passive"))
    )
    (net (code "123") (name "/HB09_P") (class "Default")
      (node (ref "J1") (pin "E27") (pinfunction "HB09_P_E27") (pintype "passive"))
    )
    (net (code "124") (name "/HB10_N") (class "Default")
      (node (ref "J1") (pin "K32") (pinfunction "HB10_N_K32") (pintype "passive"))
    )
    (net (code "125") (name "/HB10_P") (class "Default")
      (node (ref "J1") (pin "K31") (pinfunction "HB10_P_K31") (pintype "passive"))
    )
    (net (code "126") (name "/HB11_N") (class "Default")
      (node (ref "J1") (pin "J31") (pinfunction "HB11_N_J31") (pintype "passive"))
    )
    (net (code "127") (name "/HB11_P") (class "Default")
      (node (ref "J1") (pin "J30") (pinfunction "HB11_P_J30") (pintype "passive"))
    )
    (net (code "128") (name "/HB12_N") (class "Default")
      (node (ref "J1") (pin "F32") (pinfunction "HB12_N_F32") (pintype "passive"))
    )
    (net (code "129") (name "/HB12_P") (class "Default")
      (node (ref "J1") (pin "F31") (pinfunction "HB12_P_F31") (pintype "passive"))
    )
    (net (code "130") (name "/HB13_N") (class "Default")
      (node (ref "J1") (pin "E31") (pinfunction "HB13_N_E31") (pintype "passive"))
    )
    (net (code "131") (name "/HB13_P") (class "Default")
      (node (ref "J1") (pin "E30") (pinfunction "HB13_P_E30") (pintype "passive"))
    )
    (net (code "132") (name "/HB14_N") (class "Default")
      (node (ref "J1") (pin "K35") (pinfunction "HB14_N_K35") (pintype "passive"))
    )
    (net (code "133") (name "/HB14_P") (class "Default")
      (node (ref "J1") (pin "K34") (pinfunction "HB14_P_K34") (pintype "passive"))
    )
    (net (code "134") (name "/HB15_N") (class "Default")
      (node (ref "J1") (pin "J34") (pinfunction "HB15_N_J34") (pintype "passive"))
    )
    (net (code "135") (name "/HB15_P") (class "Default")
      (node (ref "J1") (pin "J33") (pinfunction "HB15_P_J33") (pintype "passive"))
    )
    (net (code "136") (name "/HB16_N") (class "Default")
      (node (ref "J1") (pin "F35") (pinfunction "HB16_N_F35") (pintype "passive"))
    )
    (net (code "137") (name "/HB16_P") (class "Default")
      (node (ref "J1") (pin "F34") (pinfunction "HB16_P_F34") (pintype "passive"))
    )
    (net (code "138") (name "/HB17_CC_N") (class "Default")
      (node (ref "J1") (pin "K38") (pinfunction "HB17_N_CC_K38") (pintype "passive"))
    )
    (net (code "139") (name "/HB17_CC_P") (class "Default")
      (node (ref "J1") (pin "K37") (pinfunction "HB17_P_CC_K37") (pintype "passive"))
    )
    (net (code "140") (name "/HB18_N") (class "Default")
      (node (ref "J1") (pin "J37") (pinfunction "HB18_N_J37") (pintype "passive"))
    )
    (net (code "141") (name "/HB18_P") (class "Default")
      (node (ref "J1") (pin "J36") (pinfunction "HB18_P_J36") (pintype "passive"))
    )
    (net (code "142") (name "/HB19_N") (class "Default")
      (node (ref "J1") (pin "E34") (pinfunction "HB19_N_E34") (pintype "passive"))
    )
    (net (code "143") (name "/HB19_P") (class "Default")
      (node (ref "J1") (pin "E33") (pinfunction "HB19_P_E33") (pintype "passive"))
    )
    (net (code "144") (name "/HB20_N") (class "Default")
      (node (ref "J1") (pin "F38") (pinfunction "HB20_N_F38") (pintype "passive"))
    )
    (net (code "145") (name "/HB20_P") (class "Default")
      (node (ref "J1") (pin "F37") (pinfunction "HB20_P_F37") (pintype "passive"))
    )
    (net (code "146") (name "/HB21_N") (class "Default")
      (node (ref "J1") (pin "E37") (pinfunction "HB21_N_E37") (pintype "passive"))
    )
    (net (code "147") (name "/HB21_P") (class "Default")
      (node (ref "J1") (pin "E36") (pinfunction "HB21_P_E36") (pintype "passive"))
    )
    (net (code "148") (name "/LA00_CC_N") (class "Default")
      (node (ref "J1") (pin "G7") (pinfunction "LA00_N_CC_G7") (pintype "passive"))
    )
    (net (code "149") (name "/LA00_CC_P") (class "Default")
      (node (ref "J1") (pin "G6") (pinfunction "LA00_P_CC_G6") (pintype "passive"))
    )
    (net (code "150") (name "/LA01_CC_N") (class "Default")
      (node (ref "J1") (pin "D9") (pinfunction "LA01_N_CC_D9") (pintype "passive"))
    )
    (net (code "151") (name "/LA01_CC_P") (class "Default")
      (node (ref "J1") (pin "D8") (pinfunction "LA01_P_CC_D8") (pintype "passive"))
    )
    (net (code "152") (name "/LA02_N") (class "Default")
      (node (ref "J1") (pin "H8") (pinfunction "LA02_N_H8") (pintype "passive"))
    )
    (net (code "153") (name "/LA02_P") (class "Default")
      (node (ref "J1") (pin "H7") (pinfunction "LA02_P_H7") (pintype "passive"))
    )
    (net (code "154") (name "/LA03_N") (class "Default")
      (node (ref "J1") (pin "G10") (pinfunction "LA03_N_G10") (pintype "passive"))
    )
    (net (code "155") (name "/LA03_P") (class "Default")
      (node (ref "J1") (pin "G9") (pinfunction "LA03_P_G9") (pintype "passive"))
    )
    (net (code "156") (name "/LA04_N") (class "Default")
      (node (ref "J1") (pin "H11") (pinfunction "LA04_N_H11") (pintype "passive"))
    )
    (net (code "157") (name "/LA04_P") (class "Default")
      (node (ref "J1") (pin "H10") (pinfunction "LA04_P_H10") (pintype "passive"))
    )
    (net (code "158") (name "/LA05_N") (class "Default")
      (node (ref "J1") (pin "D12") (pinfunction "LA05_N_D12") (pintype "passive"))
    )
    (net (code "159") (name "/LA05_P") (class "Default")
      (node (ref "J1") (pin "D11") (pinfunction "LA05_P_D11") (pintype "passive"))
    )
    (net (code "160") (name "/LA06_N") (class "Default")
      (node (ref "J1") (pin "C11") (pinfunction "LA06_N_C11") (pintype "passive"))
    )
    (net (code "161") (name "/LA06_P") (class "Default")
      (node (ref "J1") (pin "C10") (pinfunction "LA06_P_C10") (pintype "passive"))
    )
    (net (code "162") (name "/LA07_N") (class "Default")
      (node (ref "J1") (pin "H14") (pinfunction "LA07_N_H14") (pintype "passive"))
    )
    (net (code "163") (name "/LA07_P") (class "Default")
      (node (ref "J1") (pin "H13") (pinfunction "LA07_P_H13") (pintype "passive"))
    )
    (net (code "164") (name "/LA08_N") (class "Default")
      (node (ref "J1") (pin "G13") (pinfunction "LA08_N_G13") (pintype "passive"))
      (node (ref "J5") (pin "5") (pinfunction "5_5") (pintype "passive"))
    )
    (net (code "165") (name "/LA08_P") (class "Default")
      (node (ref "J1") (pin "G12") (pinfunction "LA08_P_G12") (pintype "passive"))
    )
    (net (code "166") (name "/LA09_N") (class "Default")
      (node (ref "J1") (pin "D15") (pinfunction "LA09_N_D15") (pintype "passive"))
    )
    (net (code "167") (name "/LA09_P") (class "Default")
      (node (ref "J1") (pin "D14") (pinfunction "LA09_P_D14") (pintype "passive"))
    )
    (net (code "168") (name "/LA10_N") (class "Default")
      (node (ref "J1") (pin "C15") (pinfunction "LA10_N_C15") (pintype "passive"))
    )
    (net (code "169") (name "/LA10_P") (class "Default")
      (node (ref "J1") (pin "C14") (pinfunction "LA10_P_C14") (pintype "passive"))
    )
    (net (code "170") (name "/LA11_N") (class "Default")
      (node (ref "J1") (pin "H17") (pinfunction "LA11_N_H17") (pintype "passive"))
    )
    (net (code "171") (name "/LA11_P") (class "Default")
      (node (ref "J1") (pin "H16") (pinfunction "LA11_P_H16") (pintype "passive"))
    )
    (net (code "172") (name "/LA12_N") (class "Default")
      (node (ref "J1") (pin "G16") (pinfunction "LA12_N_G16") (pintype "passive"))
    )
    (net (code "173") (name "/LA12_P") (class "Default")
      (node (ref "J1") (pin "G15") (pinfunction "LA12_P_G15") (pintype "passive"))
    )
    (net (code "174") (name "/LA13_N") (class "Default")
      (node (ref "J1") (pin "D18") (pinfunction "LA13_N_D18") (pintype "passive"))
    )
    (net (code "175") (name "/LA13_P") (class "Default")
      (node (ref "J1") (pin "D17") (pinfunction "LA13_P_D17") (pintype "passive"))
    )
    (net (code "176") (name "/LA14_N") (class "Default")
      (node (ref "J1") (pin "C19") (pinfunction "LA14_N_C19") (pintype "passive"))
    )
    (net (code "177") (name "/LA14_P") (class "Default")
      (node (ref "J1") (pin "C18") (pinfunction "LA14_P_C18") (pintype "passive"))
    )
    (net (code "178") (name "/LA15_N") (class "Default")
      (node (ref "J1") (pin "H20") (pinfunction "LA15_N_H20") (pintype "passive"))
      (node (ref "J5") (pin "4") (pinfunction "4_4") (pintype "passive"))
    )
    (net (code "179") (name "/LA15_P") (class "Default")
      (node (ref "J1") (pin "H19") (pinfunction "LA15_P_H19") (pintype "passive"))
    )
    (net (code "180") (name "/LA16_N") (class "Default")
      (node (ref "J1") (pin "G19") (pinfunction "LA16_N_G19") (pintype "passive"))
    )
    (net (code "181") (name "/LA16_P") (class "Default")
      (node (ref "J1") (pin "G18") (pinfunction "LA16_P_G18") (pintype "passive"))
    )
    (net (code "182") (name "/LA17_CC_N") (class "Default")
      (node (ref "J1") (pin "D21") (pinfunction "LA17_N_CC_D21") (pintype "passive"))
    )
    (net (code "183") (name "/LA17_CC_P") (class "Default")
      (node (ref "J1") (pin "D20") (pinfunction "LA17_P_CC_D20") (pintype "passive"))
    )
    (net (code "184") (name "/LA18_CC_N") (class "Default")
      (node (ref "J1") (pin "C23") (pinfunction "LA18_N_CC_C23") (pintype "passive"))
      (node (ref "J8") (pin "4") (pinfunction "4_4") (pintype "passive"))
    )
    (net (code "185") (name "/LA18_CC_P") (class "Default")
      (node (ref "J1") (pin "C22") (pinfunction "LA18_P_CC_C22") (pintype "passive"))
      (node (ref "J6") (pin "4") (pinfunction "4_4") (pintype "passive"))
    )
    (net (code "186") (name "/LA19_N") (class "Default")
      (node (ref "J1") (pin "H23") (pinfunction "LA19_N_H23") (pintype "passive"))
      (node (ref "J8") (pin "5") (pinfunction "5_5") (pintype "passive"))
    )
    (net (code "187") (name "/LA19_P") (class "Default")
      (node (ref "J1") (pin "H22") (pinfunction "LA19_P_H22") (pintype "passive"))
      (node (ref "J6") (pin "3") (pinfunction "3_3") (pintype "passive"))
    )
    (net (code "188") (name "/LA20_N") (class "Default")
      (node (ref "J1") (pin "G22") (pinfunction "LA20_N_G22") (pintype "passive"))
      (node (ref "J6") (pin "5") (pinfunction "5_5") (pintype "passive"))
    )
    (net (code "189") (name "/LA20_P") (class "Default")
      (node (ref "J1") (pin "G21") (pinfunction "LA20_P_G21") (pintype "passive"))
      (node (ref "J6") (pin "2") (pinfunction "2_2") (pintype "passive"))
    )
    (net (code "190") (name "/LA21_N") (class "Default")
      (node (ref "J1") (pin "H26") (pinfunction "LA21_N_H26") (pintype "passive"))
    )
    (net (code "191") (name "/LA21_P") (class "Default")
      (node (ref "J1") (pin "H25") (pinfunction "LA21_P_H25") (pintype "passive"))
    )
    (net (code "192") (name "/LA22_N") (class "Default")
      (node (ref "J1") (pin "G25") (pinfunction "LA22_N_G25") (pintype "passive"))
      (node (ref "J8") (pin "2") (pinfunction "2_2") (pintype "passive"))
    )
    (net (code "193") (name "/LA22_P") (class "Default")
      (node (ref "J1") (pin "G24") (pinfunction "LA22_P_G24") (pintype "passive"))
    )
    (net (code "194") (name "/LA23_N") (class "Default")
      (node (ref "J1") (pin "D24") (pinfunction "LA23_N_D24") (pintype "passive"))
      (node (ref "J8") (pin "3") (pinfunction "3_3") (pintype "passive"))
    )
    (net (code "195") (name "/LA23_P") (class "Default")
      (node (ref "J1") (pin "D23") (pinfunction "LA23_P_D23") (pintype "passive"))
    )
    (net (code "196") (name "/LA24_N") (class "Default")
      (node (ref "J1") (pin "H29") (pinfunction "LA24_N_H29") (pintype "passive"))
    )
    (net (code "197") (name "/LA24_P") (class "Default")
      (node (ref "J1") (pin "H28") (pinfunction "LA24_P_H28") (pintype "passive"))
    )
    (net (code "198") (name "/LA25_N") (class "Default")
      (node (ref "J1") (pin "G28") (pinfunction "LA25_N_G28") (pintype "passive"))
    )
    (net (code "199") (name "/LA25_P") (class "Default")
      (node (ref "J1") (pin "G27") (pinfunction "LA25_P_G27") (pintype "passive"))
    )
    (net (code "200") (name "/LA26_N") (class "Default")
      (node (ref "J1") (pin "D27") (pinfunction "LA26_N_D27") (pintype "passive"))
    )
    (net (code "201") (name "/LA26_P") (class "Default")
      (node (ref "J1") (pin "D26") (pinfunction "LA26_P_D26") (pintype "passive"))
    )
    (net (code "202") (name "/LA27_N") (class "Default")
      (node (ref "J1") (pin "C27") (pinfunction "LA27_N_C27") (pintype "passive"))
    )
    (net (code "203") (name "/LA27_P") (class "Default")
      (node (ref "J1") (pin "C26") (pinfunction "LA27_P_C26") (pintype "passive"))
    )
    (net (code "204") (name "/LA28_N") (class "Default")
      (node (ref "J1") (pin "H32") (pinfunction "LA28_N_H32") (pintype "passive"))
    )
    (net (code "205") (name "/LA28_P") (class "Default")
      (node (ref "J1") (pin "H31") (pinfunction "LA28_P_H31") (pintype "passive"))
    )
    (net (code "206") (name "/LA29_N") (class "Default")
      (node (ref "J1") (pin "G31") (pinfunction "LA29_N_G31") (pintype "passive"))
    )
    (net (code "207") (name "/LA29_P") (class "Default")
      (node (ref "J1") (pin "G30") (pinfunction "LA29_P_G30") (pintype "passive"))
    )
    (net (code "208") (name "/LA30_N") (class "Default")
      (node (ref "J1") (pin "H35") (pinfunction "LA30_N_H35") (pintype "passive"))
    )
    (net (code "209") (name "/LA30_P") (class "Default")
      (node (ref "J1") (pin "H34") (pinfunction "LA30_P_H34") (pintype "passive"))
    )
    (net (code "210") (name "/LA31_N") (class "Default")
      (node (ref "J1") (pin "G34") (pinfunction "LA31_N_G34") (pintype "passive"))
    )
    (net (code "211") (name "/LA31_P") (class "Default")
      (node (ref "J1") (pin "G33") (pinfunction "LA31_P_G33") (pintype "passive"))
    )
    (net (code "212") (name "/LA32_N") (class "Default")
      (node (ref "J1") (pin "H38") (pinfunction "LA32_N_H38") (pintype "passive"))
    )
    (net (code "213") (name "/LA32_P") (class "Default")
      (node (ref "J1") (pin "H37") (pinfunction "LA32_P_H37") (pintype "passive"))
    )
    (net (code "214") (name "/LA33_N") (class "Default")
      (node (ref "J1") (pin "G37") (pinfunction "LA33_N_G37") (pintype "passive"))
    )
    (net (code "215") (name "/LA33_P") (class "Default")
      (node (ref "J1") (pin "G36") (pinfunction "LA33_P_G36") (pintype "passive"))
    )
    (net (code "216") (name "/PG_C2M") (class "Default")
      (node (ref "J1") (pin "D1") (pinfunction "PG_C2M_D1") (pintype "passive"))
    )
    (net (code "217") (name "/PG_M2C") (class "Default")
      (node (ref "J1") (pin "F1") (pinfunction "PG_M2C_F1") (pintype "passive"))
    )
    (net (code "218") (name "/PRSNT_M2C_L") (class "Default")
      (node (ref "J1") (pin "H2") (pinfunction "PRSNT_M2C_L_H2") (pintype "passive"))
    )
    (net (code "219") (name "/RES0") (class "Default")
      (node (ref "J1") (pin "B40") (pinfunction "RES0_B40") (pintype "passive"))
    )
    (net (code "220") (name "/SCL") (class "Default")
      (node (ref "J1") (pin "C30") (pinfunction "SCL_C30") (pintype "passive"))
      (node (ref "R13") (pin "1") (pinfunction "1_1") (pintype "passive"))
      (node (ref "U2") (pin "1") (pinfunction "SCL_1") (pintype "input"))
    )
    (net (code "221") (name "/SDA") (class "Default")
      (node (ref "J1") (pin "C31") (pinfunction "SDA_C31") (pintype "passive"))
      (node (ref "R14") (pin "1") (pinfunction "1_1") (pintype "passive"))
      (node (ref "U2") (pin "3") (pinfunction "SDA_3") (pintype "bidirectional"))
    )
    (net (code "222") (name "/TCK") (class "Default")
      (node (ref "J1") (pin "D29") (pinfunction "TCK_D29") (pintype "passive"))
    )
    (net (code "223") (name "/TDI") (class "Default")
      (node (ref "J1") (pin "D30") (pinfunction "TDI_D30") (pintype "passive"))
    )
    (net (code "224") (name "/TDO") (class "Default")
      (node (ref "J1") (pin "D31") (pinfunction "TDO_D31") (pintype "passive"))
    )
    (net (code "225") (name "/TMS") (class "Default")
      (node (ref "J1") (pin "D33") (pinfunction "TMS_D33") (pintype "passive"))
    )
    (net (code "226") (name "/TRST_L") (class "Default")
      (node (ref "J1") (pin "D34") (pinfunction "TRST_L_D34") (pintype "passive"))
    )
    (net (code "227") (name "C-GND") (class "Default")
      (node (ref "C3") (pin "2") (pinfunction "2_2") (pintype "passive"))
      (node (ref "R6") (pin "1") (pinfunction "1_1") (pintype "passive"))
      (node (ref "X2") (pin "1") (pinfunction "1_1") (pintype "passive"))
    )
    (net (code "228") (name "GND") (class "Default")
      (node (ref "C2") (pin "2") (pinfunction "2_2") (pintype "passive"))
      (node (ref "C3") (pin "1") (pinfunction "1_1") (pintype "passive"))
      (node (ref "D1") (pin "K") (pinfunction "2_K") (pintype "passive"))
      (node (ref "D2") (pin "A") (pinfunction "A_A") (pintype "passive"))
      (node (ref "J1") (pin "A1") (pinfunction "GND_A1") (pintype "passive"))
      (node (ref "J1") (pin "A12") (pinfunction "GND_A12") (pintype "passive"))
      (node (ref "J1") (pin "A13") (pinfunction "GND_A13") (pintype "passive"))
      (node (ref "J1") (pin "A16") (pinfunction "GND_A16") (pintype "passive"))
      (node (ref "J1") (pin "A17") (pinfunction "GND_A17") (pintype "passive"))
      (node (ref "J1") (pin "A20") (pinfunction "GND_A20") (pintype "passive"))
      (node (ref "J1") (pin "A21") (pinfunction "GND_A21") (pintype "passive"))
      (node (ref "J1") (pin "A24") (pinfunction "GND_A24") (pintype "passive"))
      (node (ref "J1") (pin "A25") (pinfunction "GND_A25") (pintype "passive"))
      (node (ref "J1") (pin "A28") (pinfunction "GND_A28") (pintype "passive"))
      (node (ref "J1") (pin "A29") (pinfunction "GND_A29") (pintype "passive"))
      (node (ref "J1") (pin "A32") (pinfunction "GND_A32") (pintype "passive"))
      (node (ref "J1") (pin "A33") (pinfunction "GND_A33") (pintype "passive"))
      (node (ref "J1") (pin "A36") (pinfunction "GND_A36") (pintype "passive"))
      (node (ref "J1") (pin "A37") (pinfunction "GND_A37") (pintype "passive"))
      (node (ref "J1") (pin "A4") (pinfunction "GND_A4") (pintype "passive"))
      (node (ref "J1") (pin "A40") (pinfunction "GND_A40") (pintype "passive"))
      (node (ref "J1") (pin "A5") (pinfunction "GND_A5") (pintype "passive"))
      (node (ref "J1") (pin "A8") (pinfunction "GND_A8") (pintype "passive"))
      (node (ref "J1") (pin "A9") (pinfunction "GND_A9") (pintype "passive"))
      (node (ref "J1") (pin "B10") (pinfunction "GND_B10") (pintype "passive"))
      (node (ref "J1") (pin "B11") (pinfunction "GND_B11") (pintype "passive"))
      (node (ref "J1") (pin "B14") (pinfunction "GND_B14") (pintype "passive"))
      (node (ref "J1") (pin "B15") (pinfunction "GND_B15") (pintype "passive"))
      (node (ref "J1") (pin "B18") (pinfunction "GND_B18") (pintype "passive"))
      (node (ref "J1") (pin "B19") (pinfunction "GND_B19") (pintype "passive"))
      (node (ref "J1") (pin "B2") (pinfunction "GND_B2") (pintype "passive"))
      (node (ref "J1") (pin "B22") (pinfunction "GND_B22") (pintype "passive"))
      (node (ref "J1") (pin "B23") (pinfunction "GND_B23") (pintype "passive"))
      (node (ref "J1") (pin "B26") (pinfunction "GND_B26") (pintype "passive"))
      (node (ref "J1") (pin "B27") (pinfunction "GND_B27") (pintype "passive"))
      (node (ref "J1") (pin "B3") (pinfunction "GND_B3") (pintype "passive"))
      (node (ref "J1") (pin "B30") (pinfunction "GND_B30") (pintype "passive"))
      (node (ref "J1") (pin "B31") (pinfunction "GND_B31") (pintype "passive"))
      (node (ref "J1") (pin "B34") (pinfunction "GND_B34") (pintype "passive"))
      (node (ref "J1") (pin "B35") (pinfunction "GND_B35") (pintype "passive"))
      (node (ref "J1") (pin "B38") (pinfunction "GND_B38") (pintype "passive"))
      (node (ref "J1") (pin "B39") (pinfunction "GND_B39") (pintype "passive"))
      (node (ref "J1") (pin "B6") (pinfunction "GND_B6") (pintype "passive"))
      (node (ref "J1") (pin "B7") (pinfunction "GND_B7") (pintype "passive"))
      (node (ref "J1") (pin "C1") (pinfunction "GND_C1") (pintype "passive"))
      (node (ref "J1") (pin "C12") (pinfunction "GND_C12") (pintype "passive"))
      (node (ref "J1") (pin "C13") (pinfunction "GND_C13") (pintype "passive"))
      (node (ref "J1") (pin "C16") (pinfunction "GND_C16") (pintype "passive"))
      (node (ref "J1") (pin "C17") (pinfunction "GND_C17") (pintype "passive"))
      (node (ref "J1") (pin "C20") (pinfunction "GND_C20") (pintype "passive"))
      (node (ref "J1") (pin "C21") (pinfunction "GND_C21") (pintype "passive"))
      (node (ref "J1") (pin "C24") (pinfunction "GND_C24") (pintype "passive"))
      (node (ref "J1") (pin "C25") (pinfunction "GND_C25") (pintype "passive"))
      (node (ref "J1") (pin "C28") (pinfunction "GND_C28") (pintype "passive"))
      (node (ref "J1") (pin "C29") (pinfunction "GND_C29") (pintype "passive"))
      (node (ref "J1") (pin "C32") (pinfunction "GND_C32") (pintype "passive"))
      (node (ref "J1") (pin "C33") (pinfunction "GND_C33") (pintype "passive"))
      (node (ref "J1") (pin "C36") (pinfunction "GND_C36") (pintype "passive"))
      (node (ref "J1") (pin "C38") (pinfunction "GND_C38") (pintype "passive"))
      (node (ref "J1") (pin "C4") (pinfunction "GND_C4") (pintype "passive"))
      (node (ref "J1") (pin "C40") (pinfunction "GND_C40") (pintype "passive"))
      (node (ref "J1") (pin "C5") (pinfunction "GND_C5") (pintype "passive"))
      (node (ref "J1") (pin "C8") (pinfunction "GND_C8") (pintype "passive"))
      (node (ref "J1") (pin "C9") (pinfunction "GND_C9") (pintype "passive"))
      (node (ref "J1") (pin "D10") (pinfunction "GND_D10") (pintype "passive"))
      (node (ref "J1") (pin "D13") (pinfunction "GND_D13") (pintype "passive"))
      (node (ref "J1") (pin "D16") (pinfunction "GND_D16") (pintype "passive"))
      (node (ref "J1") (pin "D19") (pinfunction "GND_D19") (pintype "passive"))
      (node (ref "J1") (pin "D2") (pinfunction "GND_D2") (pintype "passive"))
      (node (ref "J1") (pin "D22") (pinfunction "GND_D22") (pintype "passive"))
      (node (ref "J1") (pin "D25") (pinfunction "GND_D25") (pintype "passive"))
      (node (ref "J1") (pin "D28") (pinfunction "GND_D28") (pintype "passive"))
      (node (ref "J1") (pin "D3") (pinfunction "GND_D3") (pintype "passive"))
      (node (ref "J1") (pin "D37") (pinfunction "GND_D37") (pintype "passive"))
      (node (ref "J1") (pin "D39") (pinfunction "GND_D39") (pintype "passive"))
      (node (ref "J1") (pin "D6") (pinfunction "GND_D6") (pintype "passive"))
      (node (ref "J1") (pin "D7") (pinfunction "GND_D7") (pintype "passive"))
      (node (ref "J1") (pin "E1") (pinfunction "GND_E1") (pintype "passive"))
      (node (ref "J1") (pin "E11") (pinfunction "GND_E11") (pintype "passive"))
      (node (ref "J1") (pin "E14") (pinfunction "GND_E14") (pintype "passive"))
      (node (ref "J1") (pin "E17") (pinfunction "GND_E17") (pintype "passive"))
      (node (ref "J1") (pin "E20") (pinfunction "GND_E20") (pintype "passive"))
      (node (ref "J1") (pin "E23") (pinfunction "GND_E23") (pintype "passive"))
      (node (ref "J1") (pin "E26") (pinfunction "GND_E26") (pintype "passive"))
      (node (ref "J1") (pin "E29") (pinfunction "GND_E29") (pintype "passive"))
      (node (ref "J1") (pin "E32") (pinfunction "GND_E32") (pintype "passive"))
      (node (ref "J1") (pin "E35") (pinfunction "GND_E35") (pintype "passive"))
      (node (ref "J1") (pin "E38") (pinfunction "GND_E38") (pintype "passive"))
      (node (ref "J1") (pin "E4") (pinfunction "GND_E4") (pintype "passive"))
      (node (ref "J1") (pin "E40") (pinfunction "GND_E40") (pintype "passive"))
      (node (ref "J1") (pin "E5") (pinfunction "GND_E5") (pintype "passive"))
      (node (ref "J1") (pin "E8") (pinfunction "GND_E8") (pintype "passive"))
      (node (ref "J1") (pin "F12") (pinfunction "GND_F12") (pintype "passive"))
      (node (ref "J1") (pin "F15") (pinfunction "GND_F15") (pintype "passive"))
      (node (ref "J1") (pin "F18") (pinfunction "GND_F18") (pintype "passive"))
      (node (ref "J1") (pin "F2") (pinfunction "GND_F2") (pintype "passive"))
      (node (ref "J1") (pin "F21") (pinfunction "GND_F21") (pintype "passive"))
      (node (ref "J1") (pin "F24") (pinfunction "GND_F24") (pintype "passive"))
      (node (ref "J1") (pin "F27") (pinfunction "GND_F27") (pintype "passive"))
      (node (ref "J1") (pin "F3") (pinfunction "GND_F3") (pintype "passive"))
      (node (ref "J1") (pin "F30") (pinfunction "GND_F30") (pintype "passive"))
      (node (ref "J1") (pin "F33") (pinfunction "GND_F33") (pintype "passive"))
      (node (ref "J1") (pin "F36") (pinfunction "GND_F36") (pintype "passive"))
      (node (ref "J1") (pin "F39") (pinfunction "GND_F39") (pintype "passive"))
      (node (ref "J1") (pin "F6") (pinfunction "GND_F6") (pintype "passive"))
      (node (ref "J1") (pin "F9") (pinfunction "GND_F9") (pintype "passive"))
      (node (ref "J1") (pin "G1") (pinfunction "GND_G1") (pintype "passive"))
      (node (ref "J1") (pin "G11") (pinfunction "GND_G11") (pintype "passive"))
      (node (ref "J1") (pin "G14") (pinfunction "GND_G14") (pintype "passive"))
      (node (ref "J1") (pin "G17") (pinfunction "GND_G17") (pintype "passive"))
      (node (ref "J1") (pin "G20") (pinfunction "GND_G20") (pintype "passive"))
      (node (ref "J1") (pin "G23") (pinfunction "GND_G23") (pintype "passive"))
      (node (ref "J1") (pin "G26") (pinfunction "GND_G26") (pintype "passive"))
      (node (ref "J1") (pin "G29") (pinfunction "GND_G29") (pintype "passive"))
      (node (ref "J1") (pin "G32") (pinfunction "GND_G32") (pintype "passive"))
      (node (ref "J1") (pin "G35") (pinfunction "GND_G35") (pintype "passive"))
      (node (ref "J1") (pin "G38") (pinfunction "GND_G38") (pintype "passive"))
      (node (ref "J1") (pin "G4") (pinfunction "GND_G4") (pintype "passive"))
      (node (ref "J1") (pin "G40") (pinfunction "GND_G40") (pintype "passive"))
      (node (ref "J1") (pin "G5") (pinfunction "GND_G5") (pintype "passive"))
      (node (ref "J1") (pin "G8") (pinfunction "GND_G8") (pintype "passive"))
      (node (ref "J1") (pin "H12") (pinfunction "GND_H12") (pintype "passive"))
      (node (ref "J1") (pin "H15") (pinfunction "GND_H15") (pintype "passive"))
      (node (ref "J1") (pin "H18") (pinfunction "GND_H18") (pintype "passive"))
      (node (ref "J1") (pin "H21") (pinfunction "GND_H21") (pintype "passive"))
      (node (ref "J1") (pin "H24") (pinfunction "GND_H24") (pintype "passive"))
      (node (ref "J1") (pin "H27") (pinfunction "GND_H27") (pintype "passive"))
      (node (ref "J1") (pin "H3") (pinfunction "GND_H3") (pintype "passive"))
      (node (ref "J1") (pin "H30") (pinfunction "GND_H30") (pintype "passive"))
      (node (ref "J1") (pin "H33") (pinfunction "GND_H33") (pintype "passive"))
      (node (ref "J1") (pin "H36") (pinfunction "GND_H36") (pintype "passive"))
      (node (ref "J1") (pin "H39") (pinfunction "GND_H39") (pintype "passive"))
      (node (ref "J1") (pin "H6") (pinfunction "GND_H6") (pintype "passive"))
      (node (ref "J1") (pin "H9") (pinfunction "GND_H9") (pintype "passive"))
      (node (ref "J1") (pin "J1") (pinfunction "GND_J1") (pintype "passive"))
      (node (ref "J1") (pin "J11") (pinfunction "GND_J11") (pintype "passive"))
      (node (ref "J1") (pin "J14") (pinfunction "GND_J14") (pintype "passive"))
      (node (ref "J1") (pin "J17") (pinfunction "GND_J17") (pintype "passive"))
      (node (ref "J1") (pin "J20") (pinfunction "GND_J20") (pintype "passive"))
      (node (ref "J1") (pin "J23") (pinfunction "GND_J23") (pintype "passive"))
      (node (ref "J1") (pin "J26") (pinfunction "GND_J26") (pintype "passive"))
      (node (ref "J1") (pin "J29") (pinfunction "GND_J29") (pintype "passive"))
      (node (ref "J1") (pin "J32") (pinfunction "GND_J32") (pintype "passive"))
      (node (ref "J1") (pin "J35") (pinfunction "GND_J35") (pintype "passive"))
      (node (ref "J1") (pin "J38") (pinfunction "GND_J38") (pintype "passive"))
      (node (ref "J1") (pin "J4") (pinfunction "GND_J4") (pintype "passive"))
      (node (ref "J1") (pin "J40") (pinfunction "GND_J40") (pintype "passive"))
      (node (ref "J1") (pin "J5") (pinfunction "GND_J5") (pintype "passive"))
      (node (ref "J1") (pin "J8") (pinfunction "GND_J8") (pintype "passive"))
      (node (ref "J1") (pin "K12") (pinfunction "GND_K12") (pintype "passive"))
      (node (ref "J1") (pin "K15") (pinfunction "GND_K15") (pintype "passive"))
      (node (ref "J1") (pin "K18") (pinfunction "GND_K18") (pintype "passive"))
      (node (ref "J1") (pin "K2") (pinfunction "GND_K2") (pintype "passive"))
      (node (ref "J1") (pin "K21") (pinfunction "GND_K21") (pintype "passive"))
      (node (ref "J1") (pin "K24") (pinfunction "GND_K24") (pintype "passive"))
      (node (ref "J1") (pin "K27") (pinfunction "GND_K27") (pintype "passive"))
      (node (ref "J1") (pin "K3") (pinfunction "GND_K3") (pintype "passive"))
      (node (ref "J1") (pin "K30") (pinfunction "GND_K30") (pintype "passive"))
      (node (ref "J1") (pin "K33") (pinfunction "GND_K33") (pintype "passive"))
      (node (ref "J1") (pin "K36") (pinfunction "GND_K36") (pintype "passive"))
      (node (ref "J1") (pin "K39") (pinfunction "GND_K39") (pintype "passive"))
      (node (ref "J1") (pin "K6") (pinfunction "GND_K6") (pintype "passive"))
      (node (ref "J1") (pin "K9") (pinfunction "GND_K9") (pintype "passive"))
      (node (ref "J2") (pin "2") (pinfunction "Shield_2") (pintype "passive"))
      (node (ref "J2") (pin "3") (pinfunction "Shunt_3") (pintype "passive"))
      (node (ref "J5") (pin "6") (pinfunction "6_6") (pintype "passive"))
      (node (ref "J6") (pin "6") (pinfunction "6_6") (pintype "passive"))
      (node (ref "J8") (pin "6") (pinfunction "6_6") (pintype "passive"))
      (node (ref "R12") (pin "2") (pinfunction "2_2") (pintype "passive"))
      (node (ref "R15") (pin "2") (pinfunction "2_2") (pintype "passive"))
      (node (ref "R16") (pin "2") (pinfunction "2_2") (pintype "passive"))
      (node (ref "R32") (pin "1") (pinfunction "1_1") (pintype "passive"))
      (node (ref "R6") (pin "2") (pinfunction "2_2") (pintype "passive"))
      (node (ref "U1") (pin "10") (pinfunction "IN-_10") (pintype "input"))
      (node (ref "U1") (pin "11") (pinfunction "IN+_11") (pintype "input"))
      (node (ref "U1") (pin "12") (pinfunction "GND_12") (pintype "power_in"))
      (node (ref "U2") (pin "2") (pinfunction "VSS_2") (pintype "passive"))
    )
    (net (code "229") (name "Net-(D1-1)") (class "Default")
      (node (ref "D1") (pin "A") (pinfunction "1_A") (pintype "passive"))
      (node (ref "R2") (pin "2") (pinfunction "2_2") (pintype "passive"))
    )
    (net (code "230") (name "Net-(D3-Pad1)") (class "Default")
      (node (ref "D3") (pin "1") (pinfunction "1_1") (pintype "passive"))
      (node (ref "R8") (pin "2") (pinfunction "2_2") (pintype "passive"))
    )
    (net (code "231") (name "Net-(D3-Pad3)") (class "Default")
      (node (ref "D3") (pin "3") (pinfunction "3_3") (pintype "passive"))
      (node (ref "R10") (pin "2") (pinfunction "2_2") (pintype "passive"))
    )
    (net (code "232") (name "Net-(J2-DC+)") (class "Default")
      (node (ref "D2") (pin "K") (pinfunction "K_K") (pintype "passive"))
      (node (ref "J2") (pin "1") (pinfunction "DC+_1") (pintype "passive"))
      (node (ref "Q2") (pin "D") (pinfunction "D_D") (pintype "passive"))
    )
    (net (code "233") (name "Net-(Q1-B)") (class "Default")
      (node (ref "Q1") (pin "1") (pinfunction "B_1") (pintype "passive"))
      (node (ref "R9") (pin "2") (pinfunction "2_2") (pintype "passive"))
    )
    (net (code "234") (name "Net-(Q1-C)") (class "Default")
      (node (ref "Q1") (pin "3") (pinfunction "C_3") (pintype "passive"))
      (node (ref "R10") (pin "1") (pinfunction "1_1") (pintype "passive"))
      (node (ref "R5") (pin "2") (pinfunction "2_2") (pintype "passive"))
      (node (ref "U1") (pin "2") (pinfunction "OUT_2") (pintype "output"))
    )
    (net (code "235") (name "Net-(Q1-E)") (class "Default")
      (node (ref "Q1") (pin "2") (pinfunction "E_2") (pintype "passive"))
      (node (ref "R3") (pin "2") (pinfunction "2_2") (pintype "passive"))
      (node (ref "U1") (pin "14") (pinfunction "OUT_14") (pintype "output"))
    )
    (net (code "236") (name "Net-(Q2-PadG)") (class "Default")
      (node (ref "Q2") (pin "G") (pinfunction "G_G") (pintype "passive"))
      (node (ref "R31") (pin "2") (pinfunction "2_2") (pintype "passive"))
      (node (ref "R32") (pin "2") (pinfunction "2_2") (pintype "passive"))
    )
    (net (code "237") (name "Net-(U1A-IN+)") (class "Default")
      (node (ref "R1") (pin "2") (pinfunction "2_2") (pintype "passive"))
      (node (ref "R7") (pin "1") (pinfunction "1_1") (pintype "passive"))
      (node (ref "U1") (pin "5") (pinfunction "IN+_5") (pintype "input"))
    )
    (net (code "238") (name "Net-(U1B-IN+)") (class "Default")
      (node (ref "R11") (pin "1") (pinfunction "1_1") (pintype "passive"))
      (node (ref "R7") (pin "2") (pinfunction "2_2") (pintype "passive"))
      (node (ref "U1") (pin "7") (pinfunction "IN+_7") (pintype "input"))
    )
    (net (code "239") (name "Net-(U1B-OUT)") (class "Default")
      (node (ref "R4") (pin "2") (pinfunction "2_2") (pintype "passive"))
      (node (ref "R8") (pin "1") (pinfunction "1_1") (pintype "passive"))
      (node (ref "R9") (pin "1") (pinfunction "1_1") (pintype "passive"))
      (node (ref "U1") (pin "1") (pinfunction "OUT_1") (pintype "output"))
    )
    (net (code "240") (name "Net-(U1C-IN+)") (class "Default")
      (node (ref "R11") (pin "2") (pinfunction "2_2") (pintype "passive"))
      (node (ref "R12") (pin "1") (pinfunction "1_1") (pintype "passive"))
      (node (ref "U1") (pin "9") (pinfunction "IN+_9") (pintype "input"))
    )
    (net (code "241") (name "VADJ-FMC") (class "Default")
      (node (ref "J1") (pin "E39") (pinfunction "VADJ_E39") (pintype "passive"))
      (node (ref "J1") (pin "F40") (pinfunction "VADJ_F40") (pintype "passive"))
      (node (ref "J1") (pin "G39") (pinfunction "VADJ_G39") (pintype "passive"))
      (node (ref "J1") (pin "H40") (pinfunction "VADJ_H40") (pintype "passive"))
      (node (ref "J5") (pin "1") (pinfunction "1_1") (pintype "passive"))
      (node (ref "J6") (pin "1") (pinfunction "1_1") (pintype "passive"))
      (node (ref "J8") (pin "1") (pinfunction "1_1") (pintype "passive"))
      (node (ref "R17") (pin "1") (pinfunction "1_1") (pintype "passive"))
      (node (ref "U1") (pin "4") (pinfunction "IN-_4") (pintype "input"))
      (node (ref "U1") (pin "6") (pinfunction "IN-_6") (pintype "input"))
      (node (ref "U1") (pin "8") (pinfunction "IN-_8") (pintype "input"))
    )
    (net (code "242") (name "VCC1V2") (class "Default")
      (node (ref "R17") (pin "2") (pinfunction "2_2") (pintype "passive"))
    )
    (net (code "243") (name "VCC3V3") (class "Default")
      (node (ref "D3") (pin "2") (pinfunction "2_2") (pintype "passive"))
      (node (ref "D3") (pin "4") (pinfunction "4_4") (pintype "passive"))
      (node (ref "R1") (pin "1") (pinfunction "1_1") (pintype "passive"))
      (node (ref "R2") (pin "1") (pinfunction "1_1") (pintype "passive"))
      (node (ref "R3") (pin "1") (pinfunction "1_1") (pintype "passive"))
      (node (ref "R30") (pin "2") (pinfunction "2_2") (pintype "passive"))
      (node (ref "R4") (pin "1") (pinfunction "1_1") (pintype "passive"))
      (node (ref "R5") (pin "1") (pinfunction "1_1") (pintype "passive"))
      (node (ref "U1") (pin "3") (pinfunction "VCC_3") (pintype "power_in"))
    )
    (net (code "244") (name "VCC3V3-FMC") (class "Default")
      (node (ref "J1") (pin "C39") (pinfunction "3P3V_C39") (pintype "passive"))
      (node (ref "J1") (pin "D36") (pinfunction "3P3V_D36") (pintype "passive"))
      (node (ref "J1") (pin "D38") (pinfunction "3P3V_D38") (pintype "passive"))
      (node (ref "J1") (pin "D40") (pinfunction "3P3V_D40") (pintype "passive"))
      (node (ref "R30") (pin "1") (pinfunction "1_1") (pintype "passive"))
      (node (ref "TP1") (pin "1") (pinfunction "1_1") (pintype "passive"))
    )
    (net (code "245") (name "VCC3V3AUX-FMC") (class "Default")
      (node (ref "C2") (pin "1") (pinfunction "1_1") (pintype "passive"))
      (node (ref "J1") (pin "D32") (pinfunction "3P3V/AUX_D32") (pintype "passive"))
      (node (ref "R13") (pin "2") (pinfunction "2_2") (pintype "passive"))
      (node (ref "R14") (pin "2") (pinfunction "2_2") (pintype "passive"))
      (node (ref "R19") (pin "1") (pinfunction "1_1") (pintype "passive"))
      (node (ref "R20") (pin "1") (pinfunction "1_1") (pintype "passive"))
      (node (ref "TP2") (pin "1") (pinfunction "1_1") (pintype "passive"))
      (node (ref "U2") (pin "6") (pinfunction "VCC_6") (pintype "power_in"))
    )
    (net (code "246") (name "VCC5V-EXT") (class "Default")
      (node (ref "Q2") (pin "S") (pinfunction "S_S") (pintype "passive"))
      (node (ref "R31") (pin "1") (pinfunction "1_1") (pintype "passive"))
    )
    (net (code "247") (name "VCC12V-FMC") (class "Default")
      (node (ref "J1") (pin "C35") (pinfunction "12P0V_C35") (pintype "passive"))
      (node (ref "J1") (pin "C37") (pinfunction "12P0V_C37") (pintype "passive"))
      (node (ref "TP3") (pin "1") (pinfunction "1_1") (pintype "passive"))
    )
    (net (code "248") (name "VIO_B_M2C1") (class "Default")
      (node (ref "J1") (pin "J39") (pinfunction "VIO_B_M2C_J39") (pintype "passive"))
    )
    (net (code "249") (name "VIO_B_M2C2") (class "Default")
      (node (ref "J1") (pin "K40") (pinfunction "VIO_B_M2C_K40") (pintype "passive"))
    )
    (net (code "250") (name "VREF_A_M2C") (class "Default")
      (node (ref "J1") (pin "H1") (pinfunction "VREF_A_M2C_H1") (pintype "passive"))
    )
    (net (code "251") (name "VREF_B_M2C") (class "Default")
      (node (ref "J1") (pin "K1") (pinfunction "VREF_B_M2C_K1") (pintype "passive"))
    )
    (net (code "252") (name "unconnected-(U1D-OUT-Pad13)") (class "Default")
      (node (ref "U1") (pin "13") (pinfunction "OUT_13") (pintype "output+no_connect"))
    )
    (net (code "253") (name "unconnected-(X1-Pad1)") (class "Default")
      (node (ref "X1") (pin "1") (pinfunction "1_1") (pintype "passive+no_connect"))
    )
    (net (code "254") (name "unconnected-(X3-Pad1)") (class "Default")
      (node (ref "X3") (pin "1") (pinfunction "1_1") (pintype "passive+no_connect"))
    )
    (net (code "255") (name "unconnected-(X4-Pad1)") (class "Default")
      (node (ref "X4") (pin "1") (pinfunction "1_1") (pintype "passive+no_connect"))
    )
  )
)
